# untitled.net
KiCad netlist of a schematic drawn in EAGLE
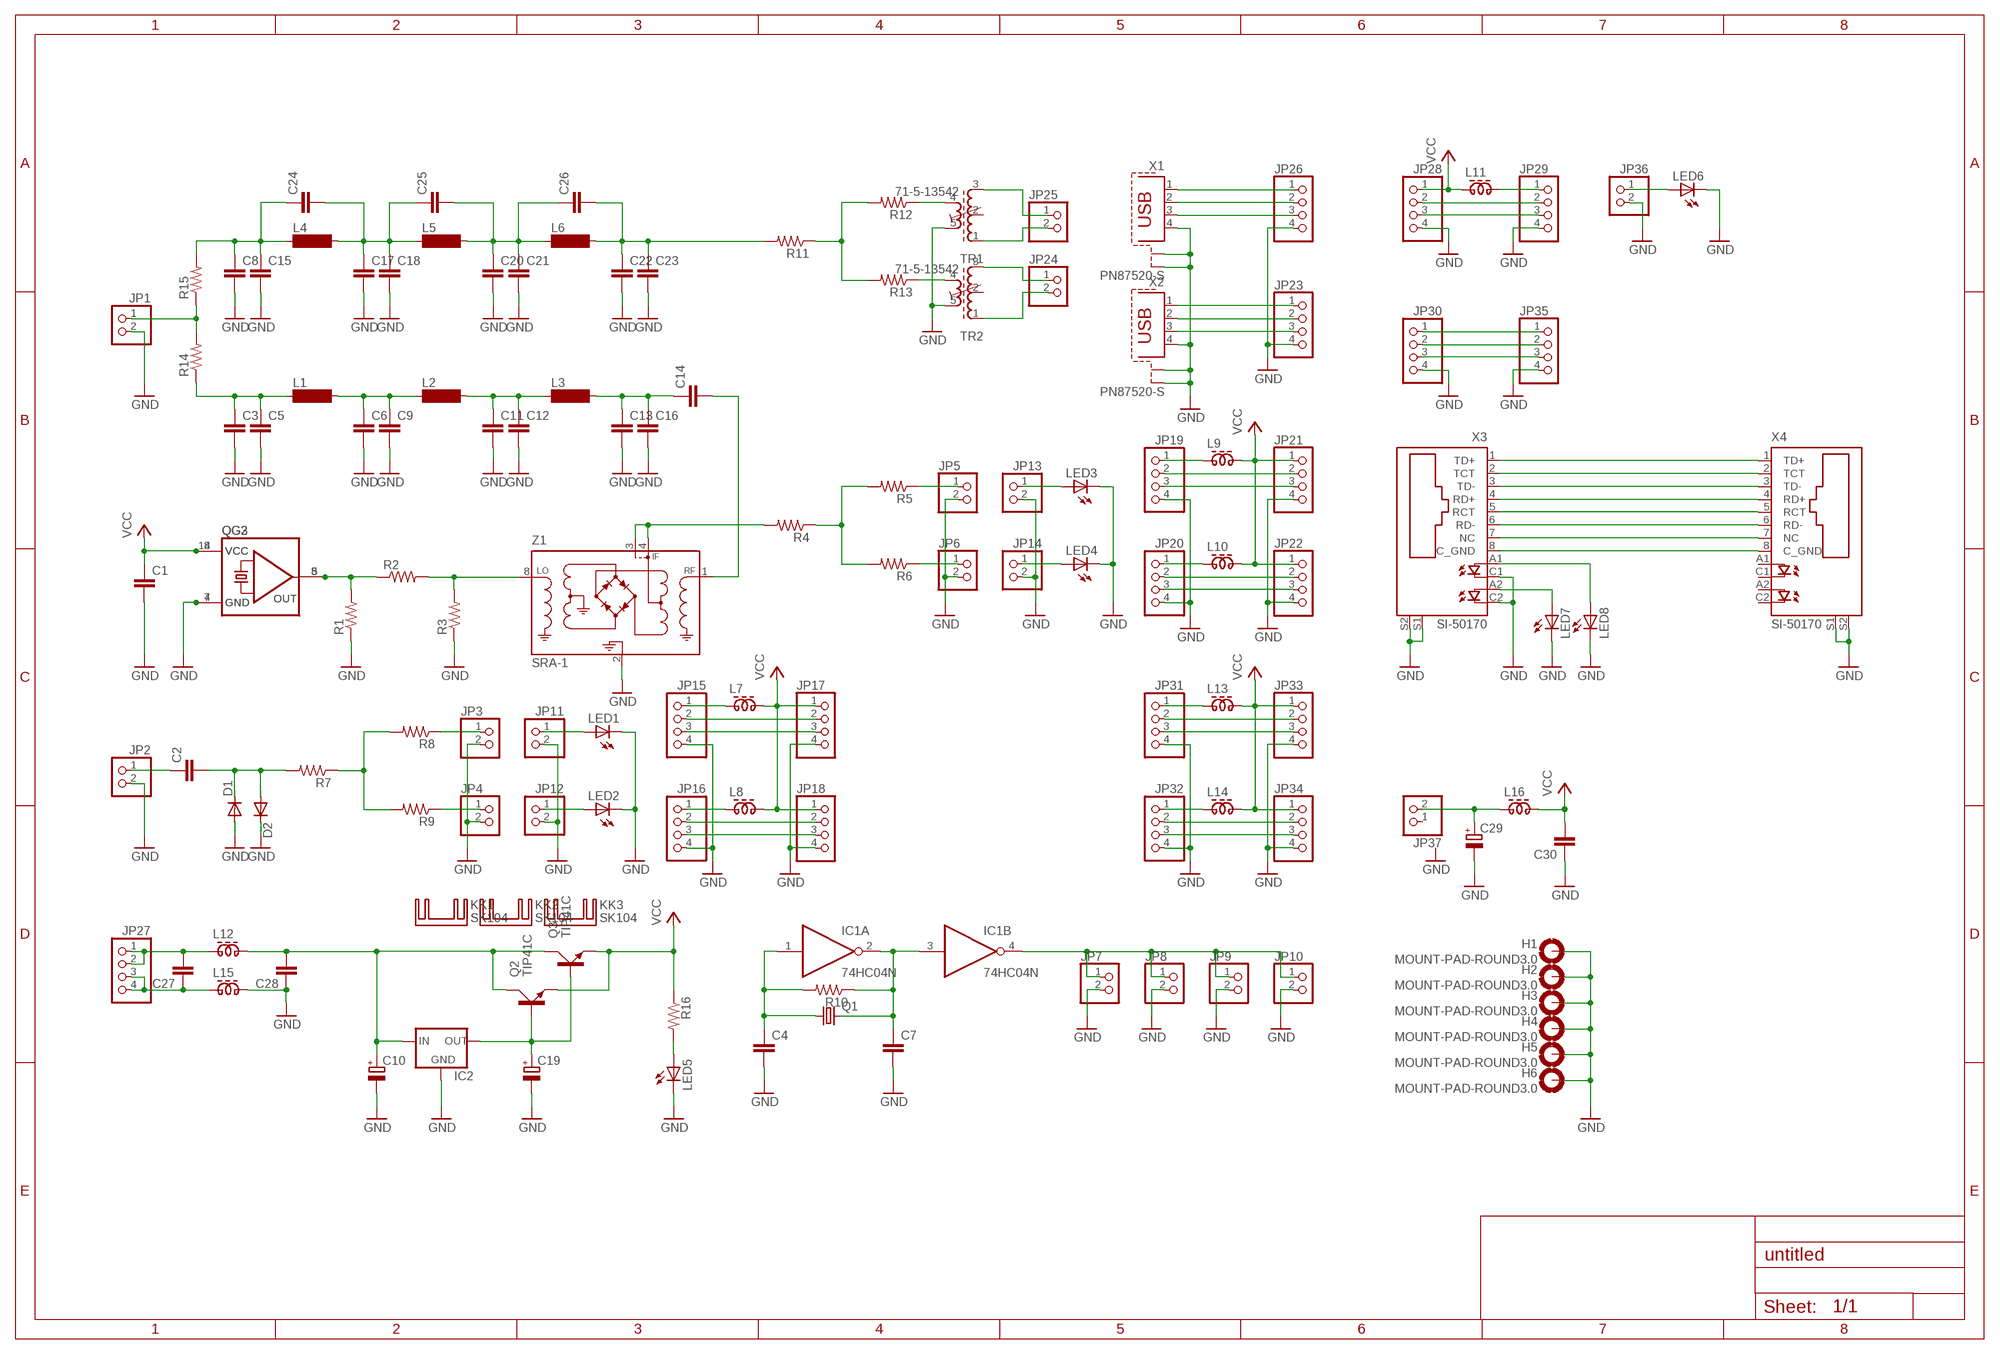
[diagram p0: schematic, sheet 1]

(export (version "E")
  (design (tool "Eeschema 10.0.6"))
  (components
    (comp (ref "C1")
      (value "C-EUC1206")
      (footprint "eagle-import:C1206")
      (libsource (lib "eagle-import") (part "C-EUC1206"))
    )
    (comp (ref "C2")
      (value "C-EUC1206")
      (footprint "eagle-import:C1206")
      (libsource (lib "eagle-import") (part "C-EUC1206"))
    )
    (comp (ref "C3")
      (value "C-EUC1206")
      (footprint "eagle-import:C1206")
      (libsource (lib "eagle-import") (part "C-EUC1206"))
    )
    (comp (ref "C4")
      (value "C-EUC1206")
      (footprint "eagle-import:C1206")
      (libsource (lib "eagle-import") (part "C-EUC1206"))
    )
    (comp (ref "C5")
      (value "C-EUC1206")
      (footprint "eagle-import:C1206")
      (libsource (lib "eagle-import") (part "C-EUC1206"))
    )
    (comp (ref "C6")
      (value "C-EUC1206")
      (footprint "eagle-import:C1206")
      (libsource (lib "eagle-import") (part "C-EUC1206"))
    )
    (comp (ref "C7")
      (value "C-EUC1206")
      (footprint "eagle-import:C1206")
      (libsource (lib "eagle-import") (part "C-EUC1206"))
    )
    (comp (ref "C8")
      (value "C-EUC1206")
      (footprint "eagle-import:C1206")
      (libsource (lib "eagle-import") (part "C-EUC1206"))
    )
    (comp (ref "C9")
      (value "C-EUC1206")
      (footprint "eagle-import:C1206")
      (libsource (lib "eagle-import") (part "C-EUC1206"))
    )
    (comp (ref "C10")
      (value "CPOL-EUE2.5-7")
      (footprint "eagle-import:E2,5-7")
      (libsource (lib "eagle-import") (part "CPOL-EUE2.5-7"))
    )
    (comp (ref "C11")
      (value "C-EUC1206")
      (footprint "eagle-import:C1206")
      (libsource (lib "eagle-import") (part "C-EUC1206"))
    )
    (comp (ref "C12")
      (value "C-EUC1206")
      (footprint "eagle-import:C1206")
      (libsource (lib "eagle-import") (part "C-EUC1206"))
    )
    (comp (ref "C13")
      (value "C-EUC1206")
      (footprint "eagle-import:C1206")
      (libsource (lib "eagle-import") (part "C-EUC1206"))
    )
    (comp (ref "C14")
      (value "C-EUC1206")
      (footprint "eagle-import:C1206")
      (libsource (lib "eagle-import") (part "C-EUC1206"))
    )
    (comp (ref "C15")
      (value "C-EUC1206")
      (footprint "eagle-import:C1206")
      (libsource (lib "eagle-import") (part "C-EUC1206"))
    )
    (comp (ref "C16")
      (value "C-EUC1206")
      (footprint "eagle-import:C1206")
      (libsource (lib "eagle-import") (part "C-EUC1206"))
    )
    (comp (ref "C17")
      (value "C-EUC1206")
      (footprint "eagle-import:C1206")
      (libsource (lib "eagle-import") (part "C-EUC1206"))
    )
    (comp (ref "C18")
      (value "C-EUC1206")
      (footprint "eagle-import:C1206")
      (libsource (lib "eagle-import") (part "C-EUC1206"))
    )
    (comp (ref "C19")
      (value "CPOL-EUE2.5-7")
      (footprint "eagle-import:E2,5-7")
      (libsource (lib "eagle-import") (part "CPOL-EUE2.5-7"))
    )
    (comp (ref "C20")
      (value "C-EUC1206")
      (footprint "eagle-import:C1206")
      (libsource (lib "eagle-import") (part "C-EUC1206"))
    )
    (comp (ref "C21")
      (value "C-EUC1206")
      (footprint "eagle-import:C1206")
      (libsource (lib "eagle-import") (part "C-EUC1206"))
    )
    (comp (ref "C22")
      (value "C-EUC1206")
      (footprint "eagle-import:C1206")
      (libsource (lib "eagle-import") (part "C-EUC1206"))
    )
    (comp (ref "C23")
      (value "C-EUC1206")
      (footprint "eagle-import:C1206")
      (libsource (lib "eagle-import") (part "C-EUC1206"))
    )
    (comp (ref "C24")
      (value "C-EUC1206")
      (footprint "eagle-import:C1206")
      (libsource (lib "eagle-import") (part "C-EUC1206"))
    )
    (comp (ref "C25")
      (value "C-EUC1206")
      (footprint "eagle-import:C1206")
      (libsource (lib "eagle-import") (part "C-EUC1206"))
    )
    (comp (ref "C26")
      (value "C-EUC1206")
      (footprint "eagle-import:C1206")
      (libsource (lib "eagle-import") (part "C-EUC1206"))
    )
    (comp (ref "C27")
      (value "C-EUC1206")
      (footprint "eagle-import:C1206")
      (libsource (lib "eagle-import") (part "C-EUC1206"))
    )
    (comp (ref "C28")
      (value "C-EUC1206")
      (footprint "eagle-import:C1206")
      (libsource (lib "eagle-import") (part "C-EUC1206"))
    )
    (comp (ref "C29")
      (value "CPOL-EUE2.5-7")
      (footprint "eagle-import:E2,5-7")
      (libsource (lib "eagle-import") (part "CPOL-EUE2.5-7"))
    )
    (comp (ref "C30")
      (value "C-EUC1206")
      (footprint "eagle-import:C1206")
      (libsource (lib "eagle-import") (part "C-EUC1206"))
    )
    (comp (ref "D1")
      (value "DIODE-DO214AC")
      (footprint "eagle-import:DO214AC")
      (libsource (lib "eagle-import") (part "DIODE-DO214AC"))
    )
    (comp (ref "D2")
      (value "DIODE-DO214AC")
      (footprint "eagle-import:DO214AC")
      (libsource (lib "eagle-import") (part "DIODE-DO214AC"))
    )
    (comp (ref "H1")
      (value "MOUNT-PAD-ROUND3.0")
      (footprint "eagle-import:3,0-PAD")
      (libsource (lib "eagle-import") (part "MOUNT-PAD-ROUND3.0"))
    )
    (comp (ref "H2")
      (value "MOUNT-PAD-ROUND3.0")
      (footprint "eagle-import:3,0-PAD")
      (libsource (lib "eagle-import") (part "MOUNT-PAD-ROUND3.0"))
    )
    (comp (ref "H3")
      (value "MOUNT-PAD-ROUND3.0")
      (footprint "eagle-import:3,0-PAD")
      (libsource (lib "eagle-import") (part "MOUNT-PAD-ROUND3.0"))
    )
    (comp (ref "H4")
      (value "MOUNT-PAD-ROUND3.0")
      (footprint "eagle-import:3,0-PAD")
      (libsource (lib "eagle-import") (part "MOUNT-PAD-ROUND3.0"))
    )
    (comp (ref "H5")
      (value "MOUNT-PAD-ROUND3.0")
      (footprint "eagle-import:3,0-PAD")
      (libsource (lib "eagle-import") (part "MOUNT-PAD-ROUND3.0"))
    )
    (comp (ref "H6")
      (value "MOUNT-PAD-ROUND3.0")
      (footprint "eagle-import:3,0-PAD")
      (libsource (lib "eagle-import") (part "MOUNT-PAD-ROUND3.0"))
    )
    (comp (ref "IC1")
      (value "74HC04N")
      (footprint "eagle-import:DIL14")
      (libsource (lib "eagle-import") (part "7404NHC"))
    )
    (comp (ref "IC2")
      (value "78XXS")
      (footprint "eagle-import:78XXS")
      (libsource (lib "eagle-import") (part "78XXS"))
    )
    (comp (ref "JP1")
      (value "PINHD-1X2")
      (footprint "eagle-import:1X02")
      (libsource (lib "eagle-import") (part "PINHD-1X2"))
    )
    (comp (ref "JP2")
      (value "PINHD-1X2")
      (footprint "eagle-import:1X02")
      (libsource (lib "eagle-import") (part "PINHD-1X2"))
    )
    (comp (ref "JP3")
      (value "PINHD-1X2")
      (footprint "eagle-import:1X02")
      (libsource (lib "eagle-import") (part "PINHD-1X2"))
    )
    (comp (ref "JP4")
      (value "PINHD-1X2")
      (footprint "eagle-import:1X02")
      (libsource (lib "eagle-import") (part "PINHD-1X2"))
    )
    (comp (ref "JP5")
      (value "PINHD-1X2")
      (footprint "eagle-import:1X02")
      (libsource (lib "eagle-import") (part "PINHD-1X2"))
    )
    (comp (ref "JP6")
      (value "PINHD-1X2")
      (footprint "eagle-import:1X02")
      (libsource (lib "eagle-import") (part "PINHD-1X2"))
    )
    (comp (ref "JP7")
      (value "PINHD-1X2")
      (footprint "eagle-import:1X02")
      (libsource (lib "eagle-import") (part "PINHD-1X2"))
    )
    (comp (ref "JP8")
      (value "PINHD-1X2")
      (footprint "eagle-import:1X02")
      (libsource (lib "eagle-import") (part "PINHD-1X2"))
    )
    (comp (ref "JP9")
      (value "PINHD-1X2")
      (footprint "eagle-import:1X02")
      (libsource (lib "eagle-import") (part "PINHD-1X2"))
    )
    (comp (ref "JP10")
      (value "PINHD-1X2")
      (footprint "eagle-import:1X02")
      (libsource (lib "eagle-import") (part "PINHD-1X2"))
    )
    (comp (ref "JP11")
      (value "PINHD-1X2")
      (footprint "eagle-import:1X02")
      (libsource (lib "eagle-import") (part "PINHD-1X2"))
    )
    (comp (ref "JP12")
      (value "PINHD-1X2")
      (footprint "eagle-import:1X02")
      (libsource (lib "eagle-import") (part "PINHD-1X2"))
    )
    (comp (ref "JP13")
      (value "PINHD-1X2")
      (footprint "eagle-import:1X02")
      (libsource (lib "eagle-import") (part "PINHD-1X2"))
    )
    (comp (ref "JP14")
      (value "PINHD-1X2")
      (footprint "eagle-import:1X02")
      (libsource (lib "eagle-import") (part "PINHD-1X2"))
    )
    (comp (ref "JP15")
      (value "PINHD-1X4")
      (footprint "eagle-import:1X04")
      (libsource (lib "eagle-import") (part "PINHD-1X4"))
    )
    (comp (ref "JP16")
      (value "PINHD-1X4")
      (footprint "eagle-import:1X04")
      (libsource (lib "eagle-import") (part "PINHD-1X4"))
    )
    (comp (ref "JP17")
      (value "PINHD-1X4")
      (footprint "eagle-import:1X04")
      (libsource (lib "eagle-import") (part "PINHD-1X4"))
    )
    (comp (ref "JP18")
      (value "PINHD-1X4")
      (footprint "eagle-import:1X04")
      (libsource (lib "eagle-import") (part "PINHD-1X4"))
    )
    (comp (ref "JP19")
      (value "PINHD-1X4")
      (footprint "eagle-import:1X04")
      (libsource (lib "eagle-import") (part "PINHD-1X4"))
    )
    (comp (ref "JP20")
      (value "PINHD-1X4")
      (footprint "eagle-import:1X04")
      (libsource (lib "eagle-import") (part "PINHD-1X4"))
    )
    (comp (ref "JP21")
      (value "PINHD-1X4")
      (footprint "eagle-import:1X04")
      (libsource (lib "eagle-import") (part "PINHD-1X4"))
    )
    (comp (ref "JP22")
      (value "PINHD-1X4")
      (footprint "eagle-import:1X04")
      (libsource (lib "eagle-import") (part "PINHD-1X4"))
    )
    (comp (ref "JP23")
      (value "PINHD-1X4")
      (footprint "eagle-import:1X04")
      (libsource (lib "eagle-import") (part "PINHD-1X4"))
    )
    (comp (ref "JP24")
      (value "PINHD-1X2")
      (footprint "eagle-import:1X02")
      (libsource (lib "eagle-import") (part "PINHD-1X2"))
    )
    (comp (ref "JP25")
      (value "PINHD-1X2")
      (footprint "eagle-import:1X02")
      (libsource (lib "eagle-import") (part "PINHD-1X2"))
    )
    (comp (ref "JP26")
      (value "PINHD-1X4")
      (footprint "eagle-import:1X04")
      (libsource (lib "eagle-import") (part "PINHD-1X4"))
    )
    (comp (ref "JP27")
      (value "PINHD-1X4")
      (footprint "eagle-import:1X04")
      (libsource (lib "eagle-import") (part "PINHD-1X4"))
    )
    (comp (ref "JP28")
      (value "PINHD-1X4")
      (footprint "eagle-import:1X04")
      (libsource (lib "eagle-import") (part "PINHD-1X4"))
    )
    (comp (ref "JP29")
      (value "PINHD-1X4")
      (footprint "eagle-import:1X04")
      (libsource (lib "eagle-import") (part "PINHD-1X4"))
    )
    (comp (ref "JP30")
      (value "PINHD-1X4")
      (footprint "eagle-import:1X04")
      (libsource (lib "eagle-import") (part "PINHD-1X4"))
    )
    (comp (ref "JP31")
      (value "PINHD-1X4")
      (footprint "eagle-import:1X04")
      (libsource (lib "eagle-import") (part "PINHD-1X4"))
    )
    (comp (ref "JP32")
      (value "PINHD-1X4")
      (footprint "eagle-import:1X04")
      (libsource (lib "eagle-import") (part "PINHD-1X4"))
    )
    (comp (ref "JP33")
      (value "PINHD-1X4")
      (footprint "eagle-import:1X04")
      (libsource (lib "eagle-import") (part "PINHD-1X4"))
    )
    (comp (ref "JP34")
      (value "PINHD-1X4")
      (footprint "eagle-import:1X04")
      (libsource (lib "eagle-import") (part "PINHD-1X4"))
    )
    (comp (ref "JP35")
      (value "PINHD-1X4")
      (footprint "eagle-import:1X04")
      (libsource (lib "eagle-import") (part "PINHD-1X4"))
    )
    (comp (ref "JP36")
      (value "PINHD-1X2")
      (footprint "eagle-import:1X02")
      (libsource (lib "eagle-import") (part "PINHD-1X2"))
    )
    (comp (ref "JP37")
      (value "PINHD-1X2")
      (footprint "eagle-import:1X02")
      (libsource (lib "eagle-import") (part "PINHD-1X2"))
    )
    (comp (ref "KK1")
      (value "SK104")
      (footprint "eagle-import:SK104")
      (libsource (lib "eagle-import") (part "SK104"))
    )
    (comp (ref "KK2")
      (value "SK104")
      (footprint "eagle-import:SK104")
      (libsource (lib "eagle-import") (part "SK104"))
    )
    (comp (ref "KK3")
      (value "SK104")
      (footprint "eagle-import:SK104")
      (libsource (lib "eagle-import") (part "SK104"))
    )
    (comp (ref "L1")
      (value "BS75")
      (footprint "eagle-import:BS75")
      (libsource (lib "eagle-import") (part "BS75"))
    )
    (comp (ref "L2")
      (value "BS75")
      (footprint "eagle-import:BS75")
      (libsource (lib "eagle-import") (part "BS75"))
    )
    (comp (ref "L3")
      (value "BS75")
      (footprint "eagle-import:BS75")
      (libsource (lib "eagle-import") (part "BS75"))
    )
    (comp (ref "L4")
      (value "BS75")
      (footprint "eagle-import:BS75")
      (libsource (lib "eagle-import") (part "BS75"))
    )
    (comp (ref "L5")
      (value "BS75")
      (footprint "eagle-import:BS75")
      (libsource (lib "eagle-import") (part "BS75"))
    )
    (comp (ref "L6")
      (value "BS75")
      (footprint "eagle-import:BS75")
      (libsource (lib "eagle-import") (part "BS75"))
    )
    (comp (ref "L7")
      (value "ZD60820512")
      (footprint "eagle-import:ZD6-2W5")
      (libsource (lib "eagle-import") (part "ZD60820512"))
    )
    (comp (ref "L8")
      (value "ZD60820512")
      (footprint "eagle-import:ZD6-2W5")
      (libsource (lib "eagle-import") (part "ZD60820512"))
    )
    (comp (ref "L9")
      (value "ZD60820512")
      (footprint "eagle-import:ZD6-2W5")
      (libsource (lib "eagle-import") (part "ZD60820512"))
    )
    (comp (ref "L10")
      (value "ZD60820512")
      (footprint "eagle-import:ZD6-2W5")
      (libsource (lib "eagle-import") (part "ZD60820512"))
    )
    (comp (ref "L11")
      (value "ZD60820512")
      (footprint "eagle-import:ZD6-2W5")
      (libsource (lib "eagle-import") (part "ZD60820512"))
    )
    (comp (ref "L12")
      (value "ZD60820512")
      (footprint "eagle-import:ZD6-2W5")
      (libsource (lib "eagle-import") (part "ZD60820512"))
    )
    (comp (ref "L13")
      (value "ZD60820512")
      (footprint "eagle-import:ZD6-2W5")
      (libsource (lib "eagle-import") (part "ZD60820512"))
    )
    (comp (ref "L14")
      (value "ZD60820512")
      (footprint "eagle-import:ZD6-2W5")
      (libsource (lib "eagle-import") (part "ZD60820512"))
    )
    (comp (ref "L15")
      (value "ZD60820512")
      (footprint "eagle-import:ZD6-2W5")
      (libsource (lib "eagle-import") (part "ZD60820512"))
    )
    (comp (ref "L16")
      (value "ZD60820512")
      (footprint "eagle-import:ZD6-2W5")
      (libsource (lib "eagle-import") (part "ZD60820512"))
    )
    (comp (ref "LED1")
      (value "LED3MM")
      (footprint "eagle-import:LED3MM")
      (libsource (lib "eagle-import") (part "LED3MM"))
    )
    (comp (ref "LED2")
      (value "LED3MM")
      (footprint "eagle-import:LED3MM")
      (libsource (lib "eagle-import") (part "LED3MM"))
    )
    (comp (ref "LED3")
      (value "LED3MM")
      (footprint "eagle-import:LED3MM")
      (libsource (lib "eagle-import") (part "LED3MM"))
    )
    (comp (ref "LED4")
      (value "LED3MM")
      (footprint "eagle-import:LED3MM")
      (libsource (lib "eagle-import") (part "LED3MM"))
    )
    (comp (ref "LED5")
      (value "LED3MM")
      (footprint "eagle-import:LED3MM")
      (libsource (lib "eagle-import") (part "LED3MM"))
    )
    (comp (ref "LED6")
      (value "LED3MM")
      (footprint "eagle-import:LED3MM")
      (libsource (lib "eagle-import") (part "LED3MM"))
    )
    (comp (ref "LED7")
      (value "LED3MM")
      (footprint "eagle-import:LED3MM")
      (libsource (lib "eagle-import") (part "LED3MM"))
    )
    (comp (ref "LED8")
      (value "LED3MM")
      (footprint "eagle-import:LED3MM")
      (libsource (lib "eagle-import") (part "LED3MM"))
    )
    (comp (ref "Q1")
      (value "CRYSTALHC49S")
      (footprint "eagle-import:HC49_S")
      (libsource (lib "eagle-import") (part "CRYSTALHC49S"))
    )
    (comp (ref "Q2")
      (value "TIP41C")
      (footprint "eagle-import:TO220AV")
      (libsource (lib "eagle-import") (part "TIP41C"))
    )
    (comp (ref "Q3")
      (value "TIP41C")
      (footprint "eagle-import:TO220AV")
      (libsource (lib "eagle-import") (part "TIP41C"))
    )
    (comp (ref "QG2")
      (value "QG5460")
      (footprint "eagle-import:DIL08S")
      (libsource (lib "eagle-import") (part "QG5460"))
    )
    (comp (ref "QG3")
      (value "QG5860")
      (footprint "eagle-import:DIL14S")
      (libsource (lib "eagle-import") (part "QG5860"))
    )
    (comp (ref "R1")
      (value "R-US_M1206")
      (footprint "eagle-import:M1206")
      (libsource (lib "eagle-import") (part "R-US_M1206"))
    )
    (comp (ref "R2")
      (value "R-US_M1206")
      (footprint "eagle-import:M1206")
      (libsource (lib "eagle-import") (part "R-US_M1206"))
    )
    (comp (ref "R3")
      (value "R-US_M1206")
      (footprint "eagle-import:M1206")
      (libsource (lib "eagle-import") (part "R-US_M1206"))
    )
    (comp (ref "R4")
      (value "R-US_M1206")
      (footprint "eagle-import:M1206")
      (libsource (lib "eagle-import") (part "R-US_M1206"))
    )
    (comp (ref "R5")
      (value "R-US_M1206")
      (footprint "eagle-import:M1206")
      (libsource (lib "eagle-import") (part "R-US_M1206"))
    )
    (comp (ref "R6")
      (value "R-US_M1206")
      (footprint "eagle-import:M1206")
      (libsource (lib "eagle-import") (part "R-US_M1206"))
    )
    (comp (ref "R7")
      (value "R-US_M1206")
      (footprint "eagle-import:M1206")
      (libsource (lib "eagle-import") (part "R-US_M1206"))
    )
    (comp (ref "R8")
      (value "R-US_M1206")
      (footprint "eagle-import:M1206")
      (libsource (lib "eagle-import") (part "R-US_M1206"))
    )
    (comp (ref "R9")
      (value "R-US_M1206")
      (footprint "eagle-import:M1206")
      (libsource (lib "eagle-import") (part "R-US_M1206"))
    )
    (comp (ref "R10")
      (value "R-US_M1206")
      (footprint "eagle-import:M1206")
      (libsource (lib "eagle-import") (part "R-US_M1206"))
    )
    (comp (ref "R11")
      (value "R-US_M1206")
      (footprint "eagle-import:M1206")
      (libsource (lib "eagle-import") (part "R-US_M1206"))
    )
    (comp (ref "R12")
      (value "R-US_M1206")
      (footprint "eagle-import:M1206")
      (libsource (lib "eagle-import") (part "R-US_M1206"))
    )
    (comp (ref "R13")
      (value "R-US_M1206")
      (footprint "eagle-import:M1206")
      (libsource (lib "eagle-import") (part "R-US_M1206"))
    )
    (comp (ref "R14")
      (value "R-US_M1206")
      (footprint "eagle-import:M1206")
      (libsource (lib "eagle-import") (part "R-US_M1206"))
    )
    (comp (ref "R15")
      (value "R-US_M1206")
      (footprint "eagle-import:M1206")
      (libsource (lib "eagle-import") (part "R-US_M1206"))
    )
    (comp (ref "R16")
      (value "R-US_M1206")
      (footprint "eagle-import:M1206")
      (libsource (lib "eagle-import") (part "R-US_M1206"))
    )
    (comp (ref "TR1")
      (value "71-5-13542")
      (footprint "eagle-import:71-5")
      (libsource (lib "eagle-import") (part "71-5-13542"))
    )
    (comp (ref "TR2")
      (value "71-5-13542")
      (footprint "eagle-import:71-5")
      (libsource (lib "eagle-import") (part "71-5-13542"))
    )
    (comp (ref "X1")
      (value "PN87520-S")
      (footprint "eagle-import:PN87520-S")
      (libsource (lib "eagle-import") (part "PN87520-S"))
    )
    (comp (ref "X2")
      (value "PN87520-S")
      (footprint "eagle-import:PN87520-S")
      (libsource (lib "eagle-import") (part "PN87520-S"))
    )
    (comp (ref "X3")
      (value "SI-50170")
      (footprint "eagle-import:SI-50170")
      (libsource (lib "eagle-import") (part "SI-50170"))
    )
    (comp (ref "X4")
      (value "SI-50170")
      (footprint "eagle-import:SI-50170")
      (libsource (lib "eagle-import") (part "SI-50170"))
    )
    (comp (ref "Z1")
      (value "SRA-1")
      (footprint "eagle-import:A01")
      (libsource (lib "eagle-import") (part "SRA-1"))
    )
  )
  (nets
    (net (code "1") (name "GND") (class "Default")
      (node (ref "C1") (pin "2") (pinfunction "2_2") (pintype "passive"))
      (node (ref "C10") (pin "-") (pinfunction "-_-") (pintype "passive"))
      (node (ref "C11") (pin "2") (pinfunction "2_2") (pintype "passive"))
      (node (ref "C12") (pin "2") (pinfunction "2_2") (pintype "passive"))
      (node (ref "C13") (pin "2") (pinfunction "2_2") (pintype "passive"))
      (node (ref "C15") (pin "2") (pinfunction "2_2") (pintype "passive"))
      (node (ref "C16") (pin "2") (pinfunction "2_2") (pintype "passive"))
      (node (ref "C17") (pin "2") (pinfunction "2_2") (pintype "passive"))
      (node (ref "C18") (pin "2") (pinfunction "2_2") (pintype "passive"))
      (node (ref "C19") (pin "-") (pinfunction "-_-") (pintype "passive"))
      (node (ref "C20") (pin "2") (pinfunction "2_2") (pintype "passive"))
      (node (ref "C21") (pin "2") (pinfunction "2_2") (pintype "passive"))
      (node (ref "C22") (pin "2") (pinfunction "2_2") (pintype "passive"))
      (node (ref "C23") (pin "2") (pinfunction "2_2") (pintype "passive"))
      (node (ref "C28") (pin "1") (pinfunction "1_1") (pintype "passive"))
      (node (ref "C29") (pin "-") (pinfunction "-_-") (pintype "passive"))
      (node (ref "C3") (pin "2") (pinfunction "2_2") (pintype "passive"))
      (node (ref "C30") (pin "1") (pinfunction "1_1") (pintype "passive"))
      (node (ref "C4") (pin "2") (pinfunction "2_2") (pintype "passive"))
      (node (ref "C5") (pin "2") (pinfunction "2_2") (pintype "passive"))
      (node (ref "C6") (pin "2") (pinfunction "2_2") (pintype "passive"))
      (node (ref "C7") (pin "2") (pinfunction "2_2") (pintype "passive"))
      (node (ref "C8") (pin "2") (pinfunction "2_2") (pintype "passive"))
      (node (ref "C9") (pin "2") (pinfunction "2_2") (pintype "passive"))
      (node (ref "D1") (pin "A") (pinfunction "A_A") (pintype "passive"))
      (node (ref "D2") (pin "C") (pinfunction "C_C") (pintype "passive"))
      (node (ref "H1") (pin "B3,0") (pinfunction "MOUNT_B3,0") (pintype "passive"))
      (node (ref "H2") (pin "B3,0") (pinfunction "MOUNT_B3,0") (pintype "passive"))
      (node (ref "H3") (pin "B3,0") (pinfunction "MOUNT_B3,0") (pintype "passive"))
      (node (ref "H4") (pin "B3,0") (pinfunction "MOUNT_B3,0") (pintype "passive"))
      (node (ref "H5") (pin "B3,0") (pinfunction "MOUNT_B3,0") (pintype "passive"))
      (node (ref "H6") (pin "B3,0") (pinfunction "MOUNT_B3,0") (pintype "passive"))
      (node (ref "IC2") (pin "GND") (pinfunction "GND_GND") (pintype "input"))
      (node (ref "JP1") (pin "2") (pinfunction "2_2") (pintype "passive"))
      (node (ref "JP10") (pin "2") (pinfunction "2_2") (pintype "passive"))
      (node (ref "JP11") (pin "2") (pinfunction "2_2") (pintype "passive"))
      (node (ref "JP12") (pin "2") (pinfunction "2_2") (pintype "passive"))
      (node (ref "JP13") (pin "2") (pinfunction "2_2") (pintype "passive"))
      (node (ref "JP14") (pin "2") (pinfunction "2_2") (pintype "passive"))
      (node (ref "JP15") (pin "4") (pinfunction "4_4") (pintype "passive"))
      (node (ref "JP16") (pin "4") (pinfunction "4_4") (pintype "passive"))
      (node (ref "JP17") (pin "4") (pinfunction "4_4") (pintype "passive"))
      (node (ref "JP18") (pin "4") (pinfunction "4_4") (pintype "passive"))
      (node (ref "JP19") (pin "4") (pinfunction "4_4") (pintype "passive"))
      (node (ref "JP2") (pin "2") (pinfunction "2_2") (pintype "passive"))
      (node (ref "JP20") (pin "4") (pinfunction "4_4") (pintype "passive"))
      (node (ref "JP21") (pin "4") (pinfunction "4_4") (pintype "passive"))
      (node (ref "JP22") (pin "4") (pinfunction "4_4") (pintype "passive"))
      (node (ref "JP23") (pin "4") (pinfunction "4_4") (pintype "passive"))
      (node (ref "JP26") (pin "4") (pinfunction "4_4") (pintype "passive"))
      (node (ref "JP28") (pin "4") (pinfunction "4_4") (pintype "passive"))
      (node (ref "JP29") (pin "4") (pinfunction "4_4") (pintype "passive"))
      (node (ref "JP3") (pin "2") (pinfunction "2_2") (pintype "passive"))
      (node (ref "JP30") (pin "4") (pinfunction "4_4") (pintype "passive"))
      (node (ref "JP31") (pin "4") (pinfunction "4_4") (pintype "passive"))
      (node (ref "JP32") (pin "4") (pinfunction "4_4") (pintype "passive"))
      (node (ref "JP33") (pin "4") (pinfunction "4_4") (pintype "passive"))
      (node (ref "JP34") (pin "4") (pinfunction "4_4") (pintype "passive"))
      (node (ref "JP35") (pin "4") (pinfunction "4_4") (pintype "passive"))
      (node (ref "JP36") (pin "2") (pinfunction "2_2") (pintype "passive"))
      (node (ref "JP4") (pin "2") (pinfunction "2_2") (pintype "passive"))
      (node (ref "JP5") (pin "2") (pinfunction "2_2") (pintype "passive"))
      (node (ref "JP6") (pin "2") (pinfunction "2_2") (pintype "passive"))
      (node (ref "JP7") (pin "2") (pinfunction "2_2") (pintype "passive"))
      (node (ref "JP8") (pin "2") (pinfunction "2_2") (pintype "passive"))
      (node (ref "JP9") (pin "2") (pinfunction "2_2") (pintype "passive"))
      (node (ref "L15") (pin "2") (pinfunction "2_2") (pintype "passive"))
      (node (ref "LED1") (pin "K") (pinfunction "C_K") (pintype "passive"))
      (node (ref "LED2") (pin "K") (pinfunction "C_K") (pintype "passive"))
      (node (ref "LED3") (pin "K") (pinfunction "C_K") (pintype "passive"))
      (node (ref "LED4") (pin "K") (pinfunction "C_K") (pintype "passive"))
      (node (ref "LED5") (pin "K") (pinfunction "C_K") (pintype "passive"))
      (node (ref "LED6") (pin "K") (pinfunction "C_K") (pintype "passive"))
      (node (ref "LED7") (pin "K") (pinfunction "C_K") (pintype "passive"))
      (node (ref "LED8") (pin "K") (pinfunction "C_K") (pintype "passive"))
      (node (ref "QG2") (pin "4") (pinfunction "GND_4") (pintype "power_in"))
      (node (ref "QG3") (pin "7") (pinfunction "GND_7") (pintype "power_in"))
      (node (ref "R1") (pin "1") (pinfunction "1_1") (pintype "passive"))
      (node (ref "R3") (pin "1") (pinfunction "1_1") (pintype "passive"))
      (node (ref "TR1") (pin "5") (pinfunction "A2_5") (pintype "passive"))
      (node (ref "TR2") (pin "5") (pinfunction "A2_5") (pintype "passive"))
      (node (ref "X1") (pin "4") (pinfunction "4_4") (pintype "passive"))
      (node (ref "X1") (pin "S1") (pinfunction "S1_S1") (pintype "passive"))
      (node (ref "X1") (pin "S2") (pinfunction "S2_S2") (pintype "passive"))
      (node (ref "X2") (pin "4") (pinfunction "4_4") (pintype "passive"))
      (node (ref "X2") (pin "S1") (pinfunction "S1_S1") (pintype "passive"))
      (node (ref "X2") (pin "S2") (pinfunction "S2_S2") (pintype "passive"))
      (node (ref "X3") (pin "C1") (pinfunction "C_C1") (pintype "passive"))
      (node (ref "X3") (pin "C2") (pinfunction "C1_C2") (pintype "passive"))
      (node (ref "X3") (pin "S1") (pinfunction "S1_S1") (pintype "passive"))
      (node (ref "X3") (pin "S2") (pinfunction "S2_S2") (pintype "passive"))
      (node (ref "X4") (pin "S1") (pinfunction "S1_S1") (pintype "passive"))
      (node (ref "X4") (pin "S2") (pinfunction "S2_S2") (pintype "passive"))
      (node (ref "Z1") (pin "2") (pinfunction "CASEGROUND_2") (pintype "passive"))
    )
    (net (code "2") (name "Net-(C2-Pad1)") (class "Default")
      (node (ref "C2") (pin "1") (pinfunction "1_1") (pintype "passive"))
      (node (ref "JP2") (pin "1") (pinfunction "1_1") (pintype "passive"))
    )
    (net (code "3") (name "Net-(C2-Pad2)") (class "Default")
      (node (ref "C2") (pin "2") (pinfunction "2_2") (pintype "passive"))
      (node (ref "D1") (pin "C") (pinfunction "C_C") (pintype "passive"))
      (node (ref "D2") (pin "A") (pinfunction "A_A") (pintype "passive"))
      (node (ref "R7") (pin "2") (pinfunction "2_2") (pintype "passive"))
    )
    (net (code "4") (name "Net-(C3-Pad1)") (class "Default")
      (node (ref "C3") (pin "1") (pinfunction "1_1") (pintype "passive"))
      (node (ref "C5") (pin "1") (pinfunction "1_1") (pintype "passive"))
      (node (ref "L1") (pin "1") (pinfunction "1_1") (pintype "passive"))
      (node (ref "R14") (pin "1") (pinfunction "1_1") (pintype "passive"))
    )
    (net (code "5") (name "Net-(C6-Pad1)") (class "Default")
      (node (ref "C6") (pin "1") (pinfunction "1_1") (pintype "passive"))
      (node (ref "C9") (pin "1") (pinfunction "1_1") (pintype "passive"))
      (node (ref "L1") (pin "2") (pinfunction "2_2") (pintype "passive"))
      (node (ref "L2") (pin "1") (pinfunction "1_1") (pintype "passive"))
    )
    (net (code "6") (name "Net-(C10-Pad+)") (class "Default")
      (node (ref "C10") (pin "+") (pinfunction "+_+") (pintype "passive"))
      (node (ref "C28") (pin "2") (pinfunction "2_2") (pintype "passive"))
      (node (ref "IC2") (pin "IN") (pinfunction "IN_IN") (pintype "input"))
      (node (ref "L12") (pin "2") (pinfunction "2_2") (pintype "passive"))
      (node (ref "Q2") (pin "C") (pinfunction "C_C") (pintype "passive"))
      (node (ref "Q3") (pin "C") (pinfunction "C_C") (pintype "passive"))
    )
    (net (code "7") (name "Net-(C11-Pad1)") (class "Default")
      (node (ref "C11") (pin "1") (pinfunction "1_1") (pintype "passive"))
      (node (ref "C12") (pin "1") (pinfunction "1_1") (pintype "passive"))
      (node (ref "L2") (pin "2") (pinfunction "2_2") (pintype "passive"))
      (node (ref "L3") (pin "1") (pinfunction "1_1") (pintype "passive"))
    )
    (net (code "8") (name "Net-(C13-Pad1)") (class "Default")
      (node (ref "C13") (pin "1") (pinfunction "1_1") (pintype "passive"))
      (node (ref "C14") (pin "1") (pinfunction "1_1") (pintype "passive"))
      (node (ref "C16") (pin "1") (pinfunction "1_1") (pintype "passive"))
      (node (ref "L3") (pin "2") (pinfunction "2_2") (pintype "passive"))
    )
    (net (code "9") (name "Net-(C15-Pad1)") (class "Default")
      (node (ref "C15") (pin "1") (pinfunction "1_1") (pintype "passive"))
      (node (ref "C24") (pin "1") (pinfunction "1_1") (pintype "passive"))
      (node (ref "C8") (pin "1") (pinfunction "1_1") (pintype "passive"))
      (node (ref "L4") (pin "1") (pinfunction "1_1") (pintype "passive"))
      (node (ref "R15") (pin "2") (pinfunction "2_2") (pintype "passive"))
    )
    (net (code "10") (name "Net-(C17-Pad1)") (class "Default")
      (node (ref "C17") (pin "1") (pinfunction "1_1") (pintype "passive"))
      (node (ref "C18") (pin "1") (pinfunction "1_1") (pintype "passive"))
      (node (ref "C24") (pin "2") (pinfunction "2_2") (pintype "passive"))
      (node (ref "C25") (pin "1") (pinfunction "1_1") (pintype "passive"))
      (node (ref "L4") (pin "2") (pinfunction "2_2") (pintype "passive"))
      (node (ref "L5") (pin "1") (pinfunction "1_1") (pintype "passive"))
    )
    (net (code "11") (name "Net-(C19-Pad+)") (class "Default")
      (node (ref "C19") (pin "+") (pinfunction "+_+") (pintype "passive"))
      (node (ref "IC2") (pin "OUT") (pinfunction "OUT_OUT") (pintype "passive"))
      (node (ref "Q2") (pin "B") (pinfunction "B_B") (pintype "passive"))
      (node (ref "Q3") (pin "B") (pinfunction "B_B") (pintype "passive"))
    )
    (net (code "12") (name "Net-(C20-Pad1)") (class "Default")
      (node (ref "C20") (pin "1") (pinfunction "1_1") (pintype "passive"))
      (node (ref "C21") (pin "1") (pinfunction "1_1") (pintype "passive"))
      (node (ref "C25") (pin "2") (pinfunction "2_2") (pintype "passive"))
      (node (ref "C26") (pin "1") (pinfunction "1_1") (pintype "passive"))
      (node (ref "L5") (pin "2") (pinfunction "2_2") (pintype "passive"))
      (node (ref "L6") (pin "1") (pinfunction "1_1") (pintype "passive"))
    )
    (net (code "13") (name "Net-(C22-Pad1)") (class "Default")
      (node (ref "C22") (pin "1") (pinfunction "1_1") (pintype "passive"))
      (node (ref "C23") (pin "1") (pinfunction "1_1") (pintype "passive"))
      (node (ref "C26") (pin "2") (pinfunction "2_2") (pintype "passive"))
      (node (ref "L6") (pin "2") (pinfunction "2_2") (pintype "passive"))
      (node (ref "R11") (pin "2") (pinfunction "2_2") (pintype "passive"))
    )
    (net (code "14") (name "Net-(C27-Pad1)") (class "Default")
      (node (ref "C27") (pin "1") (pinfunction "1_1") (pintype "passive"))
      (node (ref "JP27") (pin "3") (pinfunction "3_3") (pintype "passive"))
      (node (ref "JP27") (pin "4") (pinfunction "4_4") (pintype "passive"))
      (node (ref "L15") (pin "1") (pinfunction "1_1") (pintype "passive"))
    )
    (net (code "15") (name "Net-(C27-Pad2)") (class "Default")
      (node (ref "C27") (pin "2") (pinfunction "2_2") (pintype "passive"))
      (node (ref "JP27") (pin "1") (pinfunction "1_1") (pintype "passive"))
      (node (ref "JP27") (pin "2") (pinfunction "2_2") (pintype "passive"))
      (node (ref "L12") (pin "1") (pinfunction "1_1") (pintype "passive"))
    )
    (net (code "16") (name "Net-(C29-Pad+)") (class "Default")
      (node (ref "C29") (pin "+") (pinfunction "+_+") (pintype "passive"))
      (node (ref "JP37") (pin "2") (pinfunction "2_2") (pintype "passive"))
      (node (ref "L16") (pin "1") (pinfunction "1_1") (pintype "passive"))
    )
    (net (code "17") (name "Net-(IC1A-I)") (class "Default")
      (node (ref "C4") (pin "1") (pinfunction "1_1") (pintype "passive"))
      (node (ref "IC1") (pin "1") (pinfunction "I_1") (pintype "input"))
      (node (ref "Q1") (pin "1") (pinfunction "1_1") (pintype "passive"))
      (node (ref "R10") (pin "2") (pinfunction "2_2") (pintype "passive"))
    )
    (net (code "18") (name "Net-(IC1A-O)") (class "Default")
      (node (ref "C7") (pin "1") (pinfunction "1_1") (pintype "passive"))
      (node (ref "IC1") (pin "2") (pinfunction "O_2") (pintype "output"))
      (node (ref "IC1") (pin "3") (pinfunction "I_3") (pintype "input"))
      (node (ref "Q1") (pin "2") (pinfunction "2_2") (pintype "passive"))
      (node (ref "R10") (pin "1") (pinfunction "1_1") (pintype "passive"))
    )
    (net (code "19") (name "Net-(IC1B-O)") (class "Default")
      (node (ref "IC1") (pin "4") (pinfunction "O_4") (pintype "output"))
      (node (ref "JP10") (pin "1") (pinfunction "1_1") (pintype "passive"))
      (node (ref "JP7") (pin "1") (pinfunction "1_1") (pintype "passive"))
      (node (ref "JP8") (pin "1") (pinfunction "1_1") (pintype "passive"))
      (node (ref "JP9") (pin "1") (pinfunction "1_1") (pintype "passive"))
    )
    (net (code "20") (name "Net-(JP1-Pad1)") (class "Default")
      (node (ref "JP1") (pin "1") (pinfunction "1_1") (pintype "passive"))
      (node (ref "R14") (pin "2") (pinfunction "2_2") (pintype "passive"))
      (node (ref "R15") (pin "1") (pinfunction "1_1") (pintype "passive"))
    )
    (net (code "21") (name "Net-(JP3-Pad1)") (class "Default")
      (node (ref "JP3") (pin "1") (pinfunction "1_1") (pintype "passive"))
      (node (ref "R8") (pin "1") (pinfunction "1_1") (pintype "passive"))
    )
    (net (code "22") (name "Net-(JP4-Pad1)") (class "Default")
      (node (ref "JP4") (pin "1") (pinfunction "1_1") (pintype "passive"))
      (node (ref "R9") (pin "1") (pinfunction "1_1") (pintype "passive"))
    )
    (net (code "23") (name "Net-(JP5-Pad1)") (class "Default")
      (node (ref "JP5") (pin "1") (pinfunction "1_1") (pintype "passive"))
      (node (ref "R5") (pin "1") (pinfunction "1_1") (pintype "passive"))
    )
    (net (code "24") (name "Net-(JP6-Pad1)") (class "Default")
      (node (ref "JP6") (pin "1") (pinfunction "1_1") (pintype "passive"))
      (node (ref "R6") (pin "1") (pinfunction "1_1") (pintype "passive"))
    )
    (net (code "25") (name "Net-(JP11-Pad1)") (class "Default")
      (node (ref "JP11") (pin "1") (pinfunction "1_1") (pintype "passive"))
      (node (ref "LED1") (pin "A") (pinfunction "A_A") (pintype "passive"))
    )
    (net (code "26") (name "Net-(JP12-Pad1)") (class "Default")
      (node (ref "JP12") (pin "1") (pinfunction "1_1") (pintype "passive"))
      (node (ref "LED2") (pin "A") (pinfunction "A_A") (pintype "passive"))
    )
    (net (code "27") (name "Net-(JP13-Pad1)") (class "Default")
      (node (ref "JP13") (pin "1") (pinfunction "1_1") (pintype "passive"))
      (node (ref "LED3") (pin "A") (pinfunction "A_A") (pintype "passive"))
    )
    (net (code "28") (name "Net-(JP14-Pad1)") (class "Default")
      (node (ref "JP14") (pin "1") (pinfunction "1_1") (pintype "passive"))
      (node (ref "LED4") (pin "A") (pinfunction "A_A") (pintype "passive"))
    )
    (net (code "29") (name "Net-(JP15-Pad1)") (class "Default")
      (node (ref "JP15") (pin "1") (pinfunction "1_1") (pintype "passive"))
      (node (ref "L7") (pin "1") (pinfunction "1_1") (pintype "passive"))
    )
    (net (code "30") (name "Net-(JP15-Pad2)") (class "Default")
      (node (ref "JP15") (pin "2") (pinfunction "2_2") (pintype "passive"))
      (node (ref "JP17") (pin "2") (pinfunction "2_2") (pintype "passive"))
    )
    (net (code "31") (name "Net-(JP15-Pad3)") (class "Default")
      (node (ref "JP15") (pin "3") (pinfunction "3_3") (pintype "passive"))
      (node (ref "JP17") (pin "3") (pinfunction "3_3") (pintype "passive"))
    )
    (net (code "32") (name "Net-(JP16-Pad1)") (class "Default")
      (node (ref "JP16") (pin "1") (pinfunction "1_1") (pintype "passive"))
      (node (ref "L8") (pin "1") (pinfunction "1_1") (pintype "passive"))
    )
    (net (code "33") (name "Net-(JP16-Pad2)") (class "Default")
      (node (ref "JP16") (pin "2") (pinfunction "2_2") (pintype "passive"))
      (node (ref "JP18") (pin "2") (pinfunction "2_2") (pintype "passive"))
    )
    (net (code "34") (name "Net-(JP16-Pad3)") (class "Default")
      (node (ref "JP16") (pin "3") (pinfunction "3_3") (pintype "passive"))
      (node (ref "JP18") (pin "3") (pinfunction "3_3") (pintype "passive"))
    )
    (net (code "35") (name "Net-(JP19-Pad1)") (class "Default")
      (node (ref "JP19") (pin "1") (pinfunction "1_1") (pintype "passive"))
      (node (ref "L9") (pin "1") (pinfunction "1_1") (pintype "passive"))
    )
    (net (code "36") (name "Net-(JP19-Pad2)") (class "Default")
      (node (ref "JP19") (pin "2") (pinfunction "2_2") (pintype "passive"))
      (node (ref "JP21") (pin "2") (pinfunction "2_2") (pintype "passive"))
    )
    (net (code "37") (name "Net-(JP19-Pad3)") (class "Default")
      (node (ref "JP19") (pin "3") (pinfunction "3_3") (pintype "passive"))
      (node (ref "JP21") (pin "3") (pinfunction "3_3") (pintype "passive"))
    )
    (net (code "38") (name "Net-(JP20-Pad1)") (class "Default")
      (node (ref "JP20") (pin "1") (pinfunction "1_1") (pintype "passive"))
      (node (ref "L10") (pin "1") (pinfunction "1_1") (pintype "passive"))
    )
    (net (code "39") (name "Net-(JP20-Pad2)") (class "Default")
      (node (ref "JP20") (pin "2") (pinfunction "2_2") (pintype "passive"))
      (node (ref "JP22") (pin "2") (pinfunction "2_2") (pintype "passive"))
    )
    (net (code "40") (name "Net-(JP20-Pad3)") (class "Default")
      (node (ref "JP20") (pin "3") (pinfunction "3_3") (pintype "passive"))
      (node (ref "JP22") (pin "3") (pinfunction "3_3") (pintype "passive"))
    )
    (net (code "41") (name "Net-(JP23-Pad1)") (class "Default")
      (node (ref "JP23") (pin "1") (pinfunction "1_1") (pintype "passive"))
      (node (ref "X2") (pin "1") (pinfunction "1_1") (pintype "passive"))
    )
    (net (code "42") (name "Net-(JP23-Pad2)") (class "Default")
      (node (ref "JP23") (pin "2") (pinfunction "2_2") (pintype "passive"))
      (node (ref "X2") (pin "2") (pinfunction "2_2") (pintype "passive"))
    )
    (net (code "43") (name "Net-(JP23-Pad3)") (class "Default")
      (node (ref "JP23") (pin "3") (pinfunction "3_3") (pintype "passive"))
      (node (ref "X2") (pin "3") (pinfunction "3_3") (pintype "passive"))
    )
    (net (code "44") (name "Net-(JP26-Pad1)") (class "Default")
      (node (ref "JP26") (pin "1") (pinfunction "1_1") (pintype "passive"))
      (node (ref "X1") (pin "1") (pinfunction "1_1") (pintype "passive"))
    )
    (net (code "45") (name "Net-(JP26-Pad2)") (class "Default")
      (node (ref "JP26") (pin "2") (pinfunction "2_2") (pintype "passive"))
      (node (ref "X1") (pin "2") (pinfunction "2_2") (pintype "passive"))
    )
    (net (code "46") (name "Net-(JP26-Pad3)") (class "Default")
      (node (ref "JP26") (pin "3") (pinfunction "3_3") (pintype "passive"))
      (node (ref "X1") (pin "3") (pinfunction "3_3") (pintype "passive"))
    )
    (net (code "47") (name "Net-(JP28-Pad2)") (class "Default")
      (node (ref "JP28") (pin "2") (pinfunction "2_2") (pintype "passive"))
      (node (ref "JP29") (pin "2") (pinfunction "2_2") (pintype "passive"))
    )
    (net (code "48") (name "Net-(JP28-Pad3)") (class "Default")
      (node (ref "JP28") (pin "3") (pinfunction "3_3") (pintype "passive"))
      (node (ref "JP29") (pin "3") (pinfunction "3_3") (pintype "passive"))
    )
    (net (code "49") (name "Net-(JP29-Pad1)") (class "Default")
      (node (ref "JP29") (pin "1") (pinfunction "1_1") (pintype "passive"))
      (node (ref "L11") (pin "2") (pinfunction "2_2") (pintype "passive"))
    )
    (net (code "50") (name "Net-(JP30-Pad1)") (class "Default")
      (node (ref "JP30") (pin "1") (pinfunction "1_1") (pintype "passive"))
      (node (ref "JP35") (pin "1") (pinfunction "1_1") (pintype "passive"))
    )
    (net (code "51") (name "Net-(JP30-Pad2)") (class "Default")
      (node (ref "JP30") (pin "2") (pinfunction "2_2") (pintype "passive"))
      (node (ref "JP35") (pin "2") (pinfunction "2_2") (pintype "passive"))
    )
    (net (code "52") (name "Net-(JP30-Pad3)") (class "Default")
      (node (ref "JP30") (pin "3") (pinfunction "3_3") (pintype "passive"))
      (node (ref "JP35") (pin "3") (pinfunction "3_3") (pintype "passive"))
    )
    (net (code "53") (name "Net-(JP31-Pad1)") (class "Default")
      (node (ref "JP31") (pin "1") (pinfunction "1_1") (pintype "passive"))
      (node (ref "L13") (pin "1") (pinfunction "1_1") (pintype "passive"))
    )
    (net (code "54") (name "Net-(JP31-Pad2)") (class "Default")
      (node (ref "JP31") (pin "2") (pinfunction "2_2") (pintype "passive"))
      (node (ref "JP33") (pin "2") (pinfunction "2_2") (pintype "passive"))
    )
    (net (code "55") (name "Net-(JP31-Pad3)") (class "Default")
      (node (ref "JP31") (pin "3") (pinfunction "3_3") (pintype "passive"))
      (node (ref "JP33") (pin "3") (pinfunction "3_3") (pintype "passive"))
    )
    (net (code "56") (name "Net-(JP32-Pad1)") (class "Default")
      (node (ref "JP32") (pin "1") (pinfunction "1_1") (pintype "passive"))
      (node (ref "L14") (pin "1") (pinfunction "1_1") (pintype "passive"))
    )
    (net (code "57") (name "Net-(JP32-Pad2)") (class "Default")
      (node (ref "JP32") (pin "2") (pinfunction "2_2") (pintype "passive"))
      (node (ref "JP34") (pin "2") (pinfunction "2_2") (pintype "passive"))
    )
    (net (code "58") (name "Net-(JP32-Pad3)") (class "Default")
      (node (ref "JP32") (pin "3") (pinfunction "3_3") (pintype "passive"))
      (node (ref "JP34") (pin "3") (pinfunction "3_3") (pintype "passive"))
    )
    (net (code "59") (name "Net-(JP36-Pad1)") (class "Default")
      (node (ref "JP36") (pin "1") (pinfunction "1_1") (pintype "passive"))
      (node (ref "LED6") (pin "A") (pinfunction "A_A") (pintype "passive"))
    )
    (net (code "60") (name "Net-(LED5-PadA)") (class "Default")
      (node (ref "LED5") (pin "A") (pinfunction "A_A") (pintype "passive"))
      (node (ref "R16") (pin "2") (pinfunction "2_2") (pintype "passive"))
    )
    (net (code "61") (name "Net-(QG2-OUT)") (class "Default")
      (node (ref "QG2") (pin "5") (pinfunction "OUT_5") (pintype "output"))
      (node (ref "QG3") (pin "8") (pinfunction "OUT_8") (pintype "output"))
      (node (ref "R1") (pin "2") (pinfunction "2_2") (pintype "passive"))
      (node (ref "R2") (pin "1") (pinfunction "1_1") (pintype "passive"))
    )
    (net (code "62") (name "Net-(R4-Pad1)") (class "Default")
      (node (ref "R4") (pin "1") (pinfunction "1_1") (pintype "passive"))
      (node (ref "R5") (pin "2") (pinfunction "2_2") (pintype "passive"))
      (node (ref "R6") (pin "2") (pinfunction "2_2") (pintype "passive"))
    )
    (net (code "63") (name "Net-(R4-Pad2)") (class "Default")
      (node (ref "R4") (pin "2") (pinfunction "2_2") (pintype "passive"))
      (node (ref "Z1") (pin "3") (pinfunction "IF_3") (pintype "passive"))
      (node (ref "Z1") (pin "4") (pinfunction "IF_4") (pintype "passive"))
    )
    (net (code "64") (name "Net-(R7-Pad1)") (class "Default")
      (node (ref "R7") (pin "1") (pinfunction "1_1") (pintype "passive"))
      (node (ref "R8") (pin "2") (pinfunction "2_2") (pintype "passive"))
      (node (ref "R9") (pin "2") (pinfunction "2_2") (pintype "passive"))
    )
    (net (code "65") (name "Net-(R11-Pad1)") (class "Default")
      (node (ref "R11") (pin "1") (pinfunction "1_1") (pintype "passive"))
      (node (ref "R12") (pin "2") (pinfunction "2_2") (pintype "passive"))
      (node (ref "R13") (pin "2") (pinfunction "2_2") (pintype "passive"))
    )
    (net (code "66") (name "Net-(TR1A-A1)") (class "Default")
      (node (ref "JP25") (pin "2") (pinfunction "2_2") (pintype "passive"))
      (node (ref "TR1") (pin "1") (pinfunction "A1_1") (pintype "passive"))
    )
    (net (code "67") (name "Net-(TR1A-E1)") (class "Default")
      (node (ref "JP25") (pin "1") (pinfunction "1_1") (pintype "passive"))
      (node (ref "TR1") (pin "3") (pinfunction "E1_3") (pintype "passive"))
    )
    (net (code "68") (name "Net-(TR1A-E2)") (class "Default")
      (node (ref "R12") (pin "1") (pinfunction "1_1") (pintype "passive"))
      (node (ref "TR1") (pin "4") (pinfunction "E2_4") (pintype "passive"))
    )
    (net (code "69") (name "Net-(TR2A-A1)") (class "Default")
      (node (ref "JP24") (pin "2") (pinfunction "2_2") (pintype "passive"))
      (node (ref "TR2") (pin "1") (pinfunction "A1_1") (pintype "passive"))
    )
    (net (code "70") (name "Net-(TR2A-E1)") (class "Default")
      (node (ref "JP24") (pin "1") (pinfunction "1_1") (pintype "passive"))
      (node (ref "TR2") (pin "3") (pinfunction "E1_3") (pintype "passive"))
    )
    (net (code "71") (name "Net-(TR2A-E2)") (class "Default")
      (node (ref "R13") (pin "1") (pinfunction "1_1") (pintype "passive"))
      (node (ref "TR2") (pin "4") (pinfunction "E2_4") (pintype "passive"))
    )
    (net (code "72") (name "Net-(X3-A)") (class "Default")
      (node (ref "LED8") (pin "A") (pinfunction "A_A") (pintype "passive"))
      (node (ref "X3") (pin "A1") (pinfunction "A_A1") (pintype "passive"))
    )
    (net (code "73") (name "Net-(X3-A1)") (class "Default")
      (node (ref "LED7") (pin "A") (pinfunction "A_A") (pintype "passive"))
      (node (ref "X3") (pin "A2") (pinfunction "A1_A2") (pintype "passive"))
    )
    (net (code "74") (name "Net-(X3-C_GND)") (class "Default")
      (node (ref "X3") (pin "8") (pinfunction "C_GND_8") (pintype "passive"))
      (node (ref "X4") (pin "8") (pinfunction "C_GND_8") (pintype "passive"))
    )
    (net (code "75") (name "Net-(X3-NC)") (class "Default")
      (node (ref "X3") (pin "7") (pinfunction "NC_7") (pintype "passive"))
      (node (ref "X4") (pin "7") (pinfunction "NC_7") (pintype "passive"))
    )
    (net (code "76") (name "Net-(X3-RCT)") (class "Default")
      (node (ref "X3") (pin "5") (pinfunction "RCT_5") (pintype "passive"))
      (node (ref "X4") (pin "5") (pinfunction "RCT_5") (pintype "passive"))
    )
    (net (code "77") (name "Net-(X3-RD+)") (class "Default")
      (node (ref "X3") (pin "4") (pinfunction "RD+_4") (pintype "passive"))
      (node (ref "X4") (pin "4") (pinfunction "RD+_4") (pintype "passive"))
    )
    (net (code "78") (name "Net-(X3-RD-)") (class "Default")
      (node (ref "X3") (pin "6") (pinfunction "RD-_6") (pintype "passive"))
      (node (ref "X4") (pin "6") (pinfunction "RD-_6") (pintype "passive"))
    )
    (net (code "79") (name "Net-(X3-TCT)") (class "Default")
      (node (ref "X3") (pin "2") (pinfunction "TCT_2") (pintype "passive"))
      (node (ref "X4") (pin "2") (pinfunction "TCT_2") (pintype "passive"))
    )
    (net (code "80") (name "Net-(X3-TD+)") (class "Default")
      (node (ref "X3") (pin "1") (pinfunction "TD+_1") (pintype "passive"))
      (node (ref "X4") (pin "1") (pinfunction "TD+_1") (pintype "passive"))
    )
    (net (code "81") (name "Net-(X3-TD-)") (class "Default")
      (node (ref "X3") (pin "3") (pinfunction "TD-_3") (pintype "passive"))
      (node (ref "X4") (pin "3") (pinfunction "TD-_3") (pintype "passive"))
    )
    (net (code "82") (name "Net-(Z1A-L)") (class "Default")
      (node (ref "R2") (pin "2") (pinfunction "2_2") (pintype "passive"))
      (node (ref "R3") (pin "2") (pinfunction "2_2") (pintype "passive"))
      (node (ref "Z1") (pin "8") (pinfunction "L_8") (pintype "passive"))
    )
    (net (code "83") (name "Net-(Z1A-R)") (class "Default")
      (node (ref "C14") (pin "2") (pinfunction "2_2") (pintype "passive"))
      (node (ref "Z1") (pin "1") (pinfunction "R_1") (pintype "passive"))
    )
    (net (code "84") (name "VCC") (class "Default")
      (node (ref "C1") (pin "1") (pinfunction "1_1") (pintype "passive"))
      (node (ref "C30") (pin "2") (pinfunction "2_2") (pintype "passive"))
      (node (ref "JP17") (pin "1") (pinfunction "1_1") (pintype "passive"))
      (node (ref "JP18") (pin "1") (pinfunction "1_1") (pintype "passive"))
      (node (ref "JP21") (pin "1") (pinfunction "1_1") (pintype "passive"))
      (node (ref "JP22") (pin "1") (pinfunction "1_1") (pintype "passive"))
      (node (ref "JP28") (pin "1") (pinfunction "1_1") (pintype "passive"))
      (node (ref "JP33") (pin "1") (pinfunction "1_1") (pintype "passive"))
      (node (ref "JP34") (pin "1") (pinfunction "1_1") (pintype "passive"))
      (node (ref "L10") (pin "2") (pinfunction "2_2") (pintype "passive"))
      (node (ref "L11") (pin "1") (pinfunction "1_1") (pintype "passive"))
      (node (ref "L13") (pin "2") (pinfunction "2_2") (pintype "passive"))
      (node (ref "L14") (pin "2") (pinfunction "2_2") (pintype "passive"))
      (node (ref "L16") (pin "2") (pinfunction "2_2") (pintype "passive"))
      (node (ref "L7") (pin "2") (pinfunction "2_2") (pintype "passive"))
      (node (ref "L8") (pin "2") (pinfunction "2_2") (pintype "passive"))
      (node (ref "L9") (pin "2") (pinfunction "2_2") (pintype "passive"))
      (node (ref "Q2") (pin "E") (pinfunction "E_E") (pintype "passive"))
      (node (ref "Q3") (pin "E") (pinfunction "E_E") (pintype "passive"))
      (node (ref "QG2") (pin "8") (pinfunction "VCC_8") (pintype "power_in"))
      (node (ref "QG3") (pin "14") (pinfunction "VCC_14") (pintype "power_in"))
      (node (ref "R16") (pin "1") (pinfunction "1_1") (pintype "passive"))
    )
    (net (code "85") (name "unconnected-(JP37-Pad1)") (class "Default")
      (node (ref "JP37") (pin "1") (pinfunction "1_1") (pintype "passive"))
    )
    (net (code "86") (name "unconnected-(TR1A-Z-Pad2)") (class "Default")
      (node (ref "TR1") (pin "2") (pinfunction "Z_2") (pintype "passive"))
    )
    (net (code "87") (name "unconnected-(TR2A-Z-Pad2)") (class "Default")
      (node (ref "TR2") (pin "2") (pinfunction "Z_2") (pintype "passive"))
    )
    (net (code "88") (name "unconnected-(X4-A-PadA1)") (class "Default")
      (node (ref "X4") (pin "A1") (pinfunction "A_A1") (pintype "passive"))
    )
    (net (code "89") (name "unconnected-(X4-A1-PadA2)") (class "Default")
      (node (ref "X4") (pin "A2") (pinfunction "A1_A2") (pintype "passive"))
    )
    (net (code "90") (name "unconnected-(X4-C-PadC1)") (class "Default")
      (node (ref "X4") (pin "C1") (pinfunction "C_C1") (pintype "passive"))
    )
    (net (code "91") (name "unconnected-(X4-C1-PadC2)") (class "Default")
      (node (ref "X4") (pin "C2") (pinfunction "C1_C2") (pintype "passive"))
    )
  )
)
